# relay.net
KiCad netlist of a schematic drawn in EAGLE
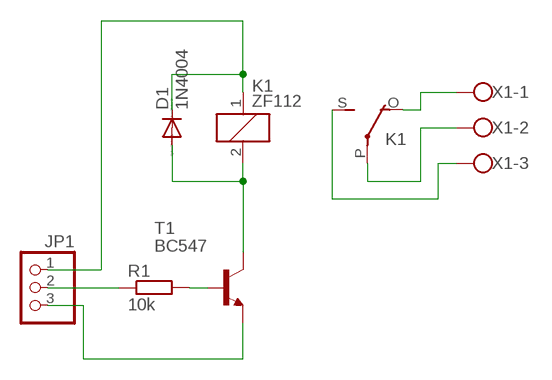
[diagram p0: schematic, sheet 1]

(export (version "E")
  (design (tool "Eeschema 10.0.6"))
  (components
    (comp (ref "D1")
      (value "1N4004")
      (footprint "eagle-import:DO41-10")
      (libsource (lib "eagle-import") (part "1N4004"))
    )
    (comp (ref "JP1")
      (value "PINHD-1X3")
      (footprint "eagle-import:1X03")
      (libsource (lib "eagle-import") (part "PINHD-1X3"))
    )
    (comp (ref "K1")
      (value "ZF112")
      (footprint "eagle-import:ZF112")
      (libsource (lib "eagle-import") (part "ZF112"))
    )
    (comp (ref "R1")
      (value "10k")
      (footprint "eagle-import:0204_7")
      (libsource (lib "eagle-import") (part "R-EU_0204/7"))
    )
    (comp (ref "T1")
      (value "BC547")
      (footprint "eagle-import:TO92")
      (libsource (lib "eagle-import") (part "BC547"))
    )
    (comp (ref "X1")
      (value "W237-103")
      (footprint "eagle-import:W237-103")
      (fields (field (name "MPN") "237-103"))
      (libsource (lib "eagle-import") (part "W237-103"))
    )
  )
  (nets
    (net (code "1") (name "Net-(D1-PadC)") (class "Default")
      (node (ref "D1") (pin "C") (pinfunction "C_C") (pintype "passive"))
      (node (ref "JP1") (pin "1") (pinfunction "1_1") (pintype "passive"))
      (node (ref "K1") (pin "1") (pinfunction "1_1") (pintype "passive"))
    )
    (net (code "2") (name "Net-(JP1-Pad2)") (class "Default")
      (node (ref "JP1") (pin "2") (pinfunction "2_2") (pintype "passive"))
      (node (ref "R1") (pin "1") (pinfunction "1_1") (pintype "passive"))
    )
    (net (code "3") (name "Net-(T1-B)") (class "Default")
      (node (ref "R1") (pin "2") (pinfunction "2_2") (pintype "passive"))
      (node (ref "T1") (pin "2") (pinfunction "B_2") (pintype "passive"))
    )
    (net (code "4") (name "Net-(T1-C)") (class "Default")
      (node (ref "D1") (pin "A") (pinfunction "A_A") (pintype "passive"))
      (node (ref "K1") (pin "2") (pinfunction "2_2") (pintype "passive"))
      (node (ref "T1") (pin "3") (pinfunction "C_3") (pintype "passive"))
    )
    (net (code "5") (name "Net-(T1-E)") (class "Default")
      (node (ref "JP1") (pin "3") (pinfunction "3_3") (pintype "passive"))
      (node (ref "T1") (pin "1") (pinfunction "E_1") (pintype "passive"))
    )
    (net (code "6") (name "Net-(X1A-KL)") (class "Default")
      (node (ref "K1") (pin "O") (pinfunction "O_O") (pintype "passive"))
      (node (ref "X1") (pin "1") (pinfunction "KL_1") (pintype "passive"))
    )
    (net (code "7") (name "Net-(X1B-KL)") (class "Default")
      (node (ref "K1") (pin "P") (pinfunction "P_P") (pintype "passive"))
      (node (ref "X1") (pin "2") (pinfunction "KL_2") (pintype "passive"))
    )
    (net (code "8") (name "Net-(X1C-KL)") (class "Default")
      (node (ref "K1") (pin "S") (pinfunction "S_S") (pintype "passive"))
      (node (ref "X1") (pin "3") (pinfunction "KL_3") (pintype "passive"))
    )
  )
)
